# Energy_Shield.net
KiCad netlist of a schematic drawn in EAGLE
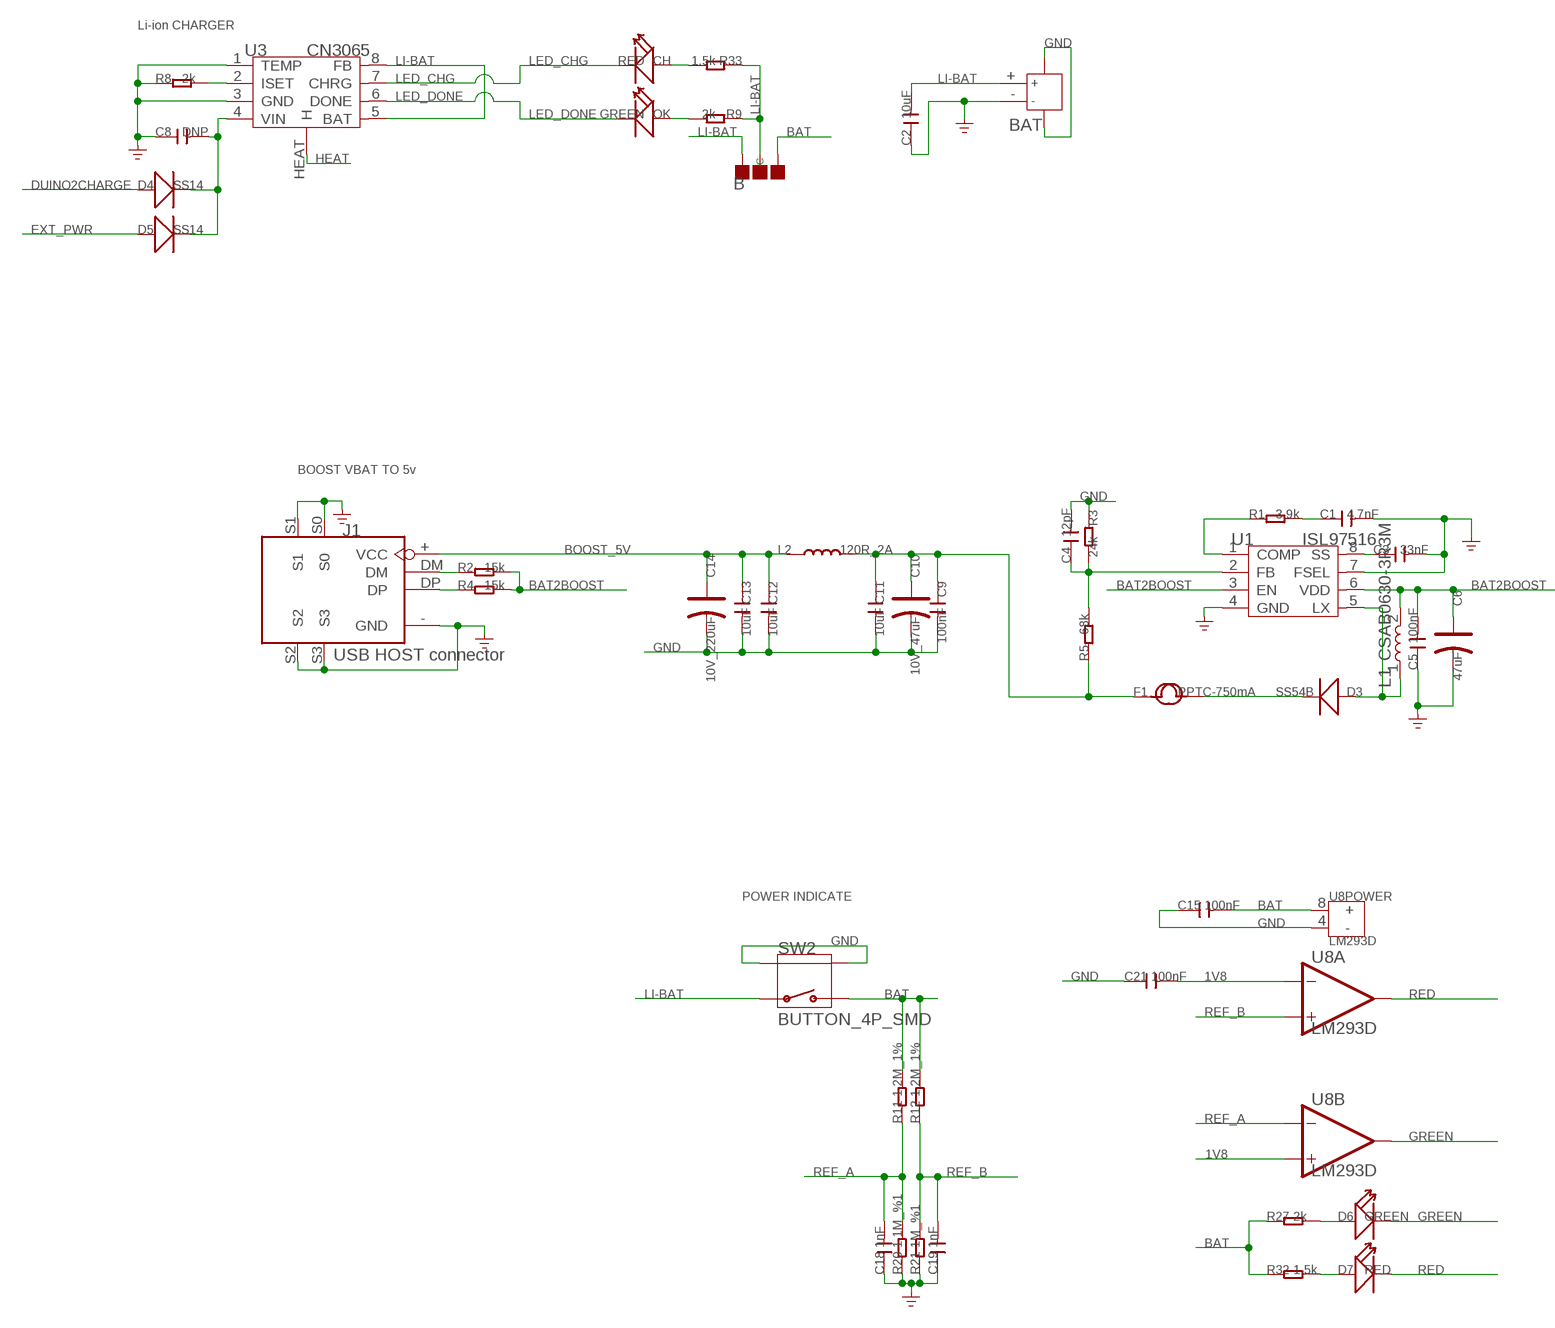
[diagram p0: schematic, sheet 1, part 1 of 2]
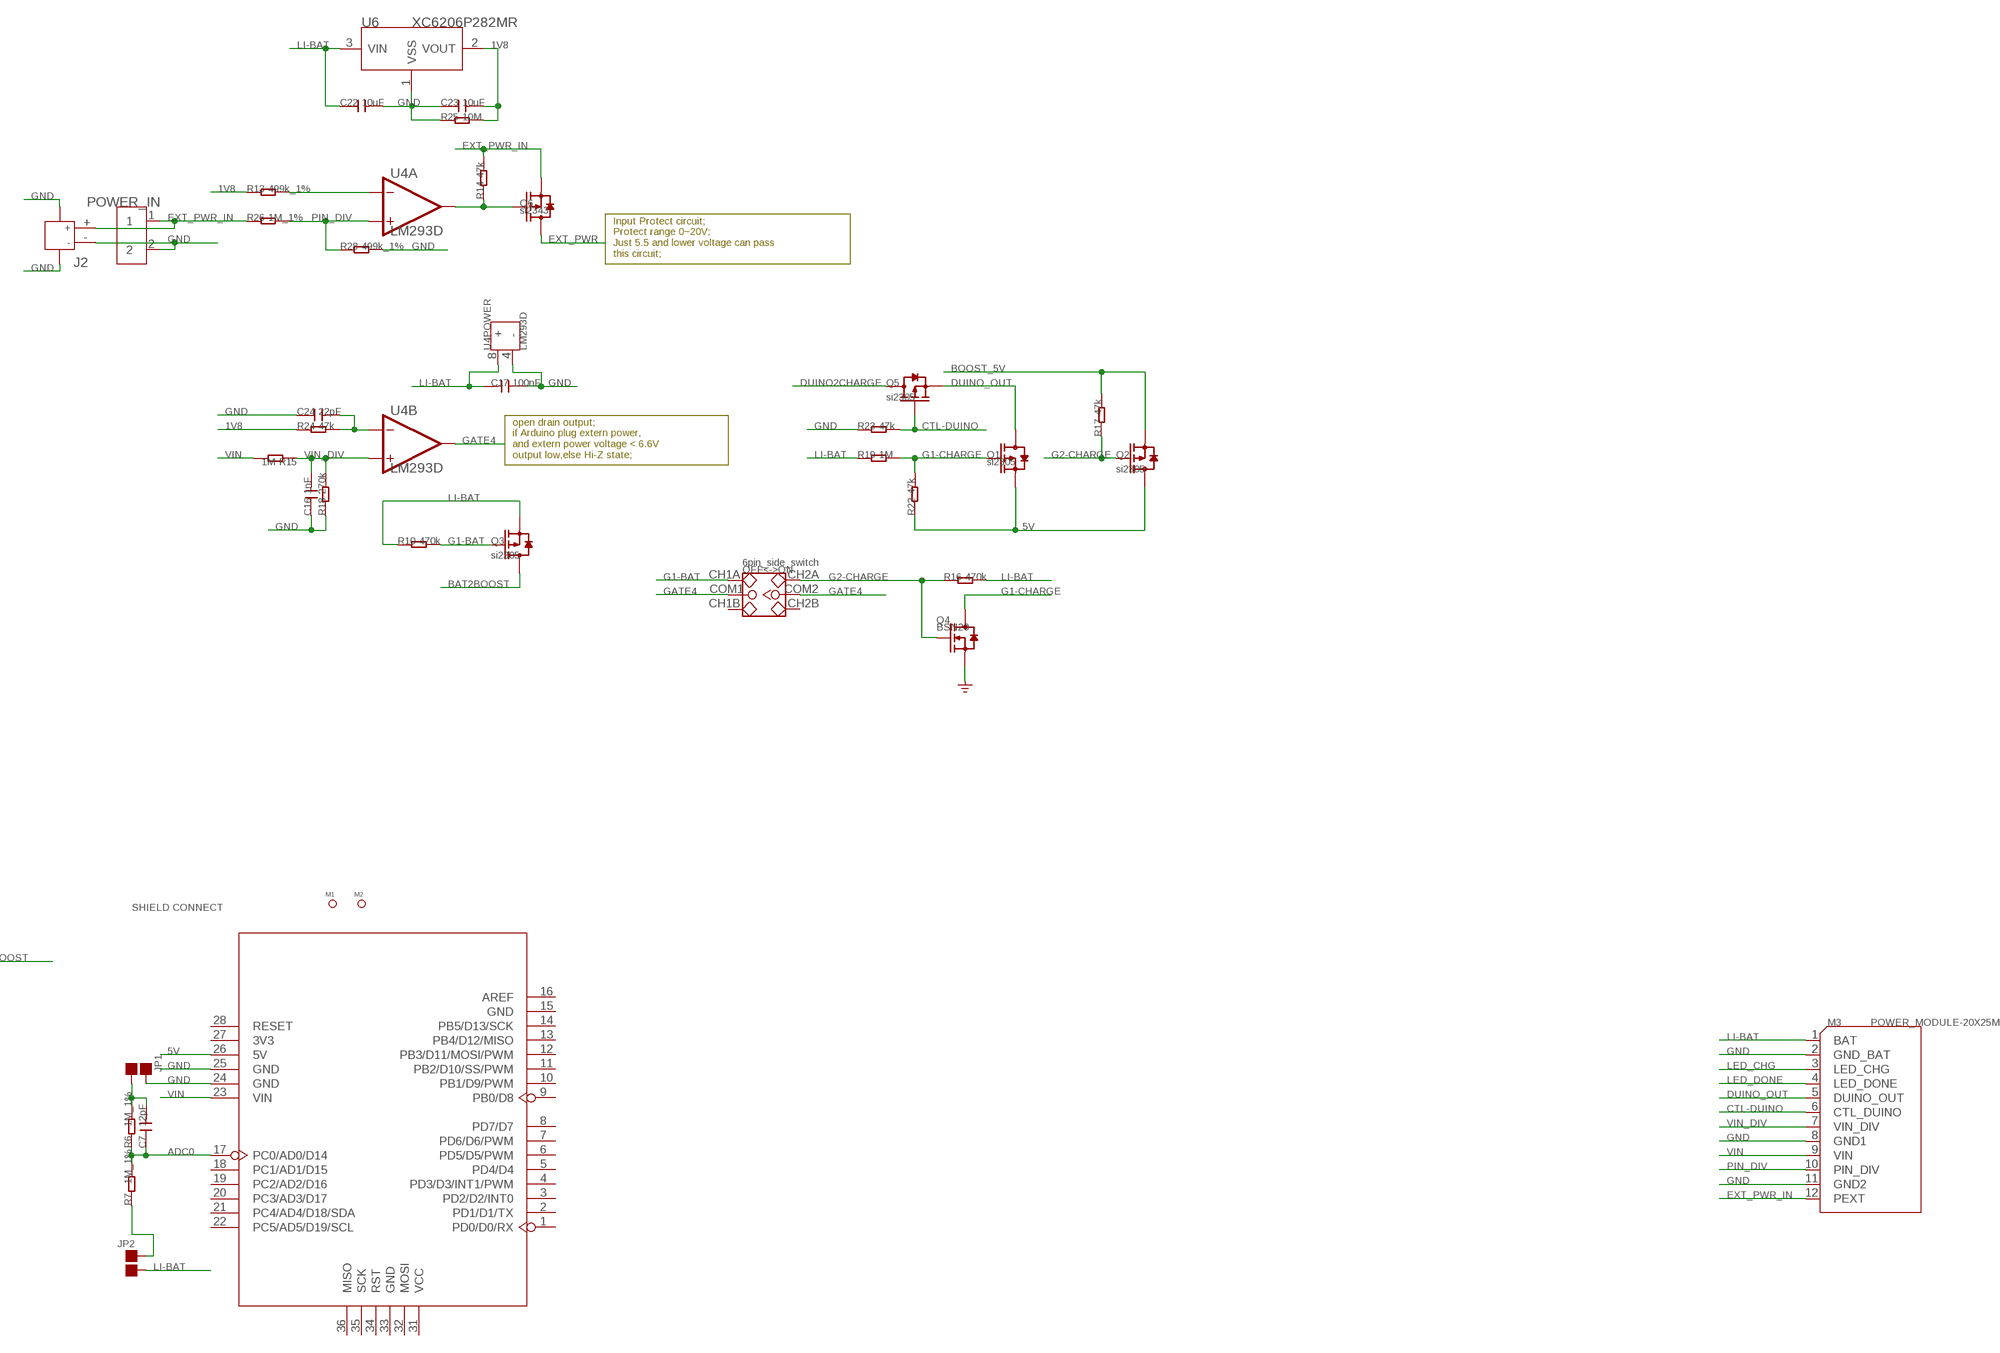
[diagram p1: schematic, sheet 1, part 2 of 2]

(export (version "E")
  (design (tool "Eeschema 10.0.6"))
  (components
    (comp (ref "B")
      (value "PAD-JUMPER-3P-40*40")
      (footprint "eagle-import:3P-SMD-4.1X1.5")
      (fields (field (name "PARTNO") "DNP"))
      (libsource (lib "eagle-import") (part "PAD-JUMPER-3P-4040"))
    )
    (comp (ref "BAT")
      (value "JACK-JST-2P-SMD-PW'2.0'")
      (footprint "eagle-import:JST-SMD-2.0-90D")
      (libsource (lib "eagle-import") (part "JACK-JST-2P-SMD-PW'2.0'"))
    )
    (comp (ref "C1")
      (value "4.7nF")
      (footprint "eagle-import:C0603")
      (libsource (lib "eagle-import") (part "C-0603"))
    )
    (comp (ref "C2")
      (value "10uF")
      (footprint "eagle-import:C0805")
      (libsource (lib "eagle-import") (part "C-0805"))
    )
    (comp (ref "C3")
      (value "33nF")
      (footprint "eagle-import:C0603")
      (libsource (lib "eagle-import") (part "C-0603"))
    )
    (comp (ref "C4")
      (value "12pF")
      (footprint "eagle-import:C0603")
      (libsource (lib "eagle-import") (part "C-0603"))
    )
    (comp (ref "C5")
      (value "100nF")
      (footprint "eagle-import:C0603")
      (libsource (lib "eagle-import") (part "C-0603"))
    )
    (comp (ref "C6")
      (value "47uF")
      (footprint "eagle-import:AVX-B")
      (libsource (lib "eagle-import") (part "CAP-AVX-B"))
    )
    (comp (ref "C7")
      (value "12pF")
      (footprint "eagle-import:C0603")
      (libsource (lib "eagle-import") (part "C-0603"))
    )
    (comp (ref "C8")
      (value "DNP")
      (footprint "eagle-import:C0805")
      (libsource (lib "eagle-import") (part "C-0805"))
    )
    (comp (ref "C9")
      (value "100nF")
      (footprint "eagle-import:C0603")
      (libsource (lib "eagle-import") (part "C-0603"))
    )
    (comp (ref "C10")
      (value "10V_47uF")
      (footprint "eagle-import:AVX-B")
      (libsource (lib "eagle-import") (part "CAP-AVX-B"))
    )
    (comp (ref "C11")
      (value "10uF")
      (footprint "eagle-import:C0805")
      (libsource (lib "eagle-import") (part "C-0805"))
    )
    (comp (ref "C12")
      (value "10uF")
      (footprint "eagle-import:C0805")
      (libsource (lib "eagle-import") (part "C-0805"))
    )
    (comp (ref "C13")
      (value "10uF")
      (footprint "eagle-import:C0805")
      (libsource (lib "eagle-import") (part "C-0805"))
    )
    (comp (ref "C14")
      (value "10V_220uF")
      (footprint "eagle-import:AVX-D")
      (libsource (lib "eagle-import") (part "CAP-AVX-D"))
    )
    (comp (ref "C15")
      (value "100nF")
      (footprint "eagle-import:C0603")
      (libsource (lib "eagle-import") (part "C-0603"))
    )
    (comp (ref "C16")
      (value "1nF")
      (footprint "eagle-import:C0603")
      (libsource (lib "eagle-import") (part "C-0603"))
    )
    (comp (ref "C17")
      (value "100nF")
      (footprint "eagle-import:C0603")
      (libsource (lib "eagle-import") (part "C-0603"))
    )
    (comp (ref "C18")
      (value "1nF")
      (footprint "eagle-import:C0603")
      (libsource (lib "eagle-import") (part "C-0603"))
    )
    (comp (ref "C19")
      (value "1nF")
      (footprint "eagle-import:C0603")
      (libsource (lib "eagle-import") (part "C-0603"))
    )
    (comp (ref "C21")
      (value "100nF")
      (footprint "eagle-import:C0603")
      (libsource (lib "eagle-import") (part "C-0603"))
    )
    (comp (ref "C22")
      (value "10uF")
      (footprint "eagle-import:C0805")
      (libsource (lib "eagle-import") (part "C-0805"))
    )
    (comp (ref "C23")
      (value "10uF")
      (footprint "eagle-import:C0805")
      (libsource (lib "eagle-import") (part "C-0805"))
    )
    (comp (ref "C24")
      (value "22pF")
      (footprint "eagle-import:C0603")
      (libsource (lib "eagle-import") (part "C-0603"))
    )
    (comp (ref "CH")
      (value "RED")
      (footprint "eagle-import:LED-SIDE-VIEW-0603-RIGHT")
      (libsource (lib "eagle-import") (part "LED'RIGHT'"))
    )
    (comp (ref "D3")
      (value "SS54B")
      (footprint "eagle-import:SMB")
      (libsource (lib "eagle-import") (part "D'MBRS240LT3'"))
    )
    (comp (ref "D4")
      (value "SS14")
      (footprint "eagle-import:D2010")
      (libsource (lib "eagle-import") (part "D'SMA'"))
    )
    (comp (ref "D5")
      (value "SS14")
      (footprint "eagle-import:D2010")
      (libsource (lib "eagle-import") (part "D'SMA'"))
    )
    (comp (ref "D6")
      (value "GREEN")
      (footprint "eagle-import:LED-SIDE-VIEW-0603-RIGHT")
      (libsource (lib "eagle-import") (part "LED'RIGHT'"))
    )
    (comp (ref "D7")
      (value "RED")
      (footprint "eagle-import:LED-SIDE-VIEW-0603-RIGHT")
      (libsource (lib "eagle-import") (part "LED'RIGHT'"))
    )
    (comp (ref "F1")
      (value "PPTC-750mA")
      (footprint "eagle-import:F1210")
      (libsource (lib "eagle-import") (part "FUSE'1210'"))
    )
    (comp (ref "J1")
      (value "USB HOST connector")
      (footprint "eagle-import:FEMALE-14.5X13.2")
      (libsource (lib "eagle-import") (part "USB-FEMALE-13.2X14.5"))
    )
    (comp (ref "J2")
      (value "JACK-JST-2P-SMD-PW'2.0'")
      (footprint "eagle-import:JST-SMD-2.0-90D")
      (libsource (lib "eagle-import") (part "JACK-JST-2P-SMD-PW'2.0'"))
    )
    (comp (ref "JP1")
      (value "PAD-JUMPER-2P")
      (footprint "eagle-import:2P-SMD-1.78X1.27")
      (fields (field (name "PARTNO") "DNP") (field (name "PARTNO_1") "DNP"))
      (libsource (lib "eagle-import") (part "PAD-JUMPER-2P"))
    )
    (comp (ref "JP2")
      (value "PAD-JUMPER-2P")
      (footprint "eagle-import:2P-SMD-1.78X1.27")
      (fields (field (name "PARTNO") "DNP"))
      (libsource (lib "eagle-import") (part "PAD-JUMPER-2P"))
    )
    (comp (ref "L1")
      (value "CSAB0630-3R3M")
      (footprint "eagle-import:L0630")
      (libsource (lib "eagle-import") (part "L"))
    )
    (comp (ref "L2")
      (value "120R_2A")
      (footprint "eagle-import:L0805")
      (libsource (lib "eagle-import") (part "L'0805'"))
    )
    (comp (ref "M1")
      (value "PAD-MARK")
      (footprint "eagle-import:ROUND-MARK-1.0")
      (fields (field (name "PARTNO") "DNP"))
      (libsource (lib "eagle-import") (part "PAD-MARK"))
    )
    (comp (ref "M2")
      (value "PAD-MARK")
      (footprint "eagle-import:ROUND-MARK-1.0")
      (fields (field (name "PARTNO") "DNP"))
      (libsource (lib "eagle-import") (part "PAD-MARK"))
    )
    (comp (ref "M3")
      (value "POWER_MODULE-20X25MM")
      (footprint "eagle-import:POWER_MODULE")
      (libsource (lib "eagle-import") (part "POWER_MODULE-20X25MM"))
    )
    (comp (ref "OFF<->ON")
      (value "6pin_side_switch")
      (footprint "eagle-import:6P-2CH-2.5-9.1X3.5X3.2H-90D")
      (libsource (lib "eagle-import") (part "SWITCH-2CH-6P'90D'"))
    )
    (comp (ref "OK")
      (value "GREEN")
      (footprint "eagle-import:LED-SIDE-VIEW-0603-RIGHT")
      (libsource (lib "eagle-import") (part "LED'RIGHT'"))
    )
    (comp (ref "POWER_IN")
      (value "SCREW-TERMINAL-2P'3.5'")
      (footprint "eagle-import:2P-3.5")
      (libsource (lib "eagle-import") (part "SCREW-TERMINAL-2P'3.5'"))
    )
    (comp (ref "Q1")
      (value "si2305")
      (footprint "eagle-import:SOT23")
      (libsource (lib "eagle-import") (part "MOSFET-P'SI2323CDS/SI2305DS{lt}BR{gt}'"))
    )
    (comp (ref "Q2")
      (value "si2305")
      (footprint "eagle-import:SOT23")
      (libsource (lib "eagle-import") (part "MOSFET-P'SI2323CDS/SI2305DS{lt}BR{gt}'"))
    )
    (comp (ref "Q3")
      (value "si2305")
      (footprint "eagle-import:SOT23")
      (libsource (lib "eagle-import") (part "MOSFET-P'SI2323CDS/SI2305DS{lt}BR{gt}'"))
    )
    (comp (ref "Q4")
      (value "BSN20")
      (footprint "eagle-import:SOT23")
      (libsource (lib "eagle-import") (part "MOSFET-N'SOT23'"))
    )
    (comp (ref "Q5")
      (value "si2305")
      (footprint "eagle-import:SOT23")
      (libsource (lib "eagle-import") (part "MOSFET-P'SI2323CDS/SI2305DS{lt}BR{gt}'"))
    )
    (comp (ref "Q6")
      (value "si2343")
      (footprint "eagle-import:SOT23")
      (libsource (lib "eagle-import") (part "MOSFET-P'SI2323CDS/SI2305DS{lt}BR{gt}'"))
    )
    (comp (ref "R1")
      (value "3.9k")
      (footprint "eagle-import:R0603")
      (libsource (lib "eagle-import") (part "R-0603"))
    )
    (comp (ref "R2")
      (value "15k")
      (footprint "eagle-import:R0603")
      (libsource (lib "eagle-import") (part "R-0603"))
    )
    (comp (ref "R3")
      (value "24k")
      (footprint "eagle-import:R0603")
      (libsource (lib "eagle-import") (part "R-0603"))
    )
    (comp (ref "R4")
      (value "15k")
      (footprint "eagle-import:R0603")
      (libsource (lib "eagle-import") (part "R-0603"))
    )
    (comp (ref "R5")
      (value "68k")
      (footprint "eagle-import:R0603")
      (libsource (lib "eagle-import") (part "R-0603"))
    )
    (comp (ref "R6")
      (value "1M_1%")
      (footprint "eagle-import:R0603")
      (libsource (lib "eagle-import") (part "R-0603"))
    )
    (comp (ref "R7")
      (value "1M_1%")
      (footprint "eagle-import:R0603")
      (libsource (lib "eagle-import") (part "R-0603"))
    )
    (comp (ref "R8")
      (value "2k")
      (footprint "eagle-import:R0603")
      (libsource (lib "eagle-import") (part "R-0603"))
    )
    (comp (ref "R9")
      (value "2k")
      (footprint "eagle-import:R0603")
      (libsource (lib "eagle-import") (part "R-0603"))
    )
    (comp (ref "R10")
      (value "470k")
      (footprint "eagle-import:R0603")
      (libsource (lib "eagle-import") (part "R-0603"))
    )
    (comp (ref "R11")
      (value "1.2M_1%")
      (footprint "eagle-import:R0603")
      (libsource (lib "eagle-import") (part "R-0603"))
    )
    (comp (ref "R12")
      (value "1.2M_1%")
      (footprint "eagle-import:R0603")
      (libsource (lib "eagle-import") (part "R-0603"))
    )
    (comp (ref "R13")
      (value "499k_1%")
      (footprint "eagle-import:R0603")
      (libsource (lib "eagle-import") (part "R-0603"))
    )
    (comp (ref "R14")
      (value "47k")
      (footprint "eagle-import:R0603")
      (libsource (lib "eagle-import") (part "R-0603"))
    )
    (comp (ref "R15")
      (value "1M")
      (footprint "eagle-import:R0603")
      (libsource (lib "eagle-import") (part "R-0603"))
    )
    (comp (ref "R16")
      (value "470k")
      (footprint "eagle-import:R0603")
      (libsource (lib "eagle-import") (part "R-0603"))
    )
    (comp (ref "R17")
      (value "47k")
      (footprint "eagle-import:R0603")
      (libsource (lib "eagle-import") (part "R-0603"))
    )
    (comp (ref "R18")
      (value "270k")
      (footprint "eagle-import:R0603")
      (libsource (lib "eagle-import") (part "R-0603"))
    )
    (comp (ref "R19")
      (value "1M")
      (footprint "eagle-import:R0603")
      (libsource (lib "eagle-import") (part "R-0603"))
    )
    (comp (ref "R20")
      (value "1.1M_%1")
      (footprint "eagle-import:R0603")
      (libsource (lib "eagle-import") (part "R-0603"))
    )
    (comp (ref "R21")
      (value "1M_%1")
      (footprint "eagle-import:R0603")
      (libsource (lib "eagle-import") (part "R-0603"))
    )
    (comp (ref "R22")
      (value "47k")
      (footprint "eagle-import:R0603")
      (libsource (lib "eagle-import") (part "R-0603"))
    )
    (comp (ref "R23")
      (value "47k")
      (footprint "eagle-import:R0603")
      (libsource (lib "eagle-import") (part "R-0603"))
    )
    (comp (ref "R24")
      (value "47k")
      (footprint "eagle-import:R0603")
      (libsource (lib "eagle-import") (part "R-0603"))
    )
    (comp (ref "R25")
      (value "10M")
      (footprint "eagle-import:R0603")
      (libsource (lib "eagle-import") (part "R-0603"))
    )
    (comp (ref "R26")
      (value "1M_1%")
      (footprint "eagle-import:R0603")
      (libsource (lib "eagle-import") (part "R-0603"))
    )
    (comp (ref "R27")
      (value "2k")
      (footprint "eagle-import:R0603")
      (libsource (lib "eagle-import") (part "R-0603"))
    )
    (comp (ref "R28")
      (value "499k_1%")
      (footprint "eagle-import:R0603")
      (libsource (lib "eagle-import") (part "R-0603"))
    )
    (comp (ref "R32")
      (value "1.5k")
      (footprint "eagle-import:R0603")
      (libsource (lib "eagle-import") (part "R-0603"))
    )
    (comp (ref "R33")
      (value "1.5k")
      (footprint "eagle-import:R0603")
      (libsource (lib "eagle-import") (part "R-0603"))
    )
    (comp (ref "SW2")
      (value "BUTTON_4P_SMD")
      (footprint "eagle-import:4P-SMD-7X3.5X3.5")
      (libsource (lib "eagle-import") (part "BUTTON_4P_SMD"))
    )
    (comp (ref "U1")
      (value "ISL97516")
      (footprint "eagle-import:MSOP8")
      (libsource (lib "eagle-import") (part "ISL97516-MSOP8"))
    )
    (comp (ref "U2")
      (value "ARDUINO'W/O-SILK'")
      (footprint "eagle-import:ARDUINO-W_O-SILK")
      (libsource (lib "eagle-import") (part "ARDUINO'W/O-SILK'"))
    )
    (comp (ref "U3")
      (value "CN3065")
      (footprint "eagle-import:DFN8")
      (libsource (lib "eagle-import") (part "CN3065-DFN8"))
    )
    (comp (ref "U4")
      (value "LM293D")
      (footprint "eagle-import:SOIC8-6.0")
      (libsource (lib "eagle-import") (part "LMX93D"))
    )
    (comp (ref "U6")
      (value "XC6206P282MR")
      (footprint "eagle-import:SOT23")
      (libsource (lib "eagle-import") (part "XC6206MR"))
    )
    (comp (ref "U8")
      (value "LM293D")
      (footprint "eagle-import:SOIC8-6.0")
      (libsource (lib "eagle-import") (part "LMX93D"))
    )
  )
  (nets
    (net (code "1") (name "/1V8") (class "Default")
      (node (ref "C21") (pin "2") (pinfunction "2_2") (pintype "passive"))
      (node (ref "C23") (pin "2") (pinfunction "2_2") (pintype "passive"))
      (node (ref "R13") (pin "1") (pinfunction "1_1") (pintype "passive"))
      (node (ref "R24") (pin "1") (pinfunction "1_1") (pintype "passive"))
      (node (ref "R25") (pin "2") (pinfunction "2_2") (pintype "passive"))
      (node (ref "U6") (pin "2") (pinfunction "VOUT_2") (pintype "output"))
      (node (ref "U8") (pin "2") (pinfunction "IN-_2") (pintype "input"))
      (node (ref "U8") (pin "5") (pinfunction "IN+_5") (pintype "input"))
    )
    (net (code "2") (name "/5V") (class "Default")
      (node (ref "Q1") (pin "2") (pinfunction "S_2") (pintype "passive"))
      (node (ref "Q2") (pin "3") (pinfunction "D_3") (pintype "passive"))
      (node (ref "R22") (pin "1") (pinfunction "1_1") (pintype "passive"))
      (node (ref "U2") (pin "26") (pinfunction "5V_26") (pintype "bidirectional"))
    )
    (net (code "3") (name "/ADC0") (class "Default")
      (node (ref "C7") (pin "1") (pinfunction "1_1") (pintype "passive"))
      (node (ref "R6") (pin "1") (pinfunction "1_1") (pintype "passive"))
      (node (ref "R7") (pin "2") (pinfunction "2_2") (pintype "passive"))
      (node (ref "U2") (pin "17") (pinfunction "PC0/AD0/D14_17") (pintype "bidirectional"))
    )
    (net (code "4") (name "/BAT") (class "Default")
      (node (ref "B") (pin "00") (pinfunction "L_00") (pintype "bidirectional"))
      (node (ref "C15") (pin "2") (pinfunction "2_2") (pintype "passive"))
      (node (ref "R11") (pin "2") (pinfunction "2_2") (pintype "passive"))
      (node (ref "R12") (pin "2") (pinfunction "2_2") (pintype "passive"))
      (node (ref "R27") (pin "1") (pinfunction "1_1") (pintype "passive"))
      (node (ref "R32") (pin "1") (pinfunction "1_1") (pintype "passive"))
      (node (ref "SW2") (pin "2") (pinfunction "2_2") (pintype "bidirectional"))
      (node (ref "U8") (pin "8") (pinfunction "+_8") (pintype "bidirectional"))
    )
    (net (code "5") (name "/BAT2BOOST") (class "Default")
      (node (ref "C5") (pin "2") (pinfunction "2_2") (pintype "passive"))
      (node (ref "C6") (pin "+") (pinfunction "+_+") (pintype "passive"))
      (node (ref "L1") (pin "2") (pinfunction "P$2_2") (pintype "bidirectional"))
      (node (ref "Q3") (pin "3") (pinfunction "D_3") (pintype "passive"))
      (node (ref "R2") (pin "2") (pinfunction "2_2") (pintype "passive"))
      (node (ref "R4") (pin "2") (pinfunction "2_2") (pintype "passive"))
      (node (ref "U1") (pin "3") (pinfunction "EN_3") (pintype "input"))
      (node (ref "U1") (pin "6") (pinfunction "VDD_6") (pintype "power_in"))
    )
    (net (code "6") (name "/BOOST_5V") (class "Default")
      (node (ref "C12") (pin "1") (pinfunction "1_1") (pintype "passive"))
      (node (ref "C13") (pin "1") (pinfunction "1_1") (pintype "passive"))
      (node (ref "C14") (pin "+") (pinfunction "+_+") (pintype "passive"))
      (node (ref "J1") (pin "+") (pinfunction "VCC_+") (pintype "bidirectional"))
      (node (ref "L2") (pin "1") (pinfunction "1_1") (pintype "passive"))
      (node (ref "Q2") (pin "2") (pinfunction "S_2") (pintype "passive"))
      (node (ref "R17") (pin "2") (pinfunction "2_2") (pintype "passive"))
    )
    (net (code "7") (name "/CTL-DUINO") (class "Default")
      (node (ref "M3") (pin "6") (pinfunction "CTL_DUINO_6") (pintype "bidirectional"))
      (node (ref "Q5") (pin "1") (pinfunction "G_1") (pintype "passive"))
      (node (ref "R23") (pin "2") (pinfunction "2_2") (pintype "passive"))
    )
    (net (code "8") (name "/DUINO2CHARGE") (class "Default")
      (node (ref "D4") (pin "+") (pinfunction "+_+") (pintype "passive"))
      (node (ref "Q5") (pin "3") (pinfunction "D_3") (pintype "passive"))
    )
    (net (code "9") (name "/DUINO_OUT") (class "Default")
      (node (ref "M3") (pin "5") (pinfunction "DUINO_OUT_5") (pintype "bidirectional"))
      (node (ref "Q1") (pin "3") (pinfunction "D_3") (pintype "passive"))
      (node (ref "Q5") (pin "2") (pinfunction "S_2") (pintype "passive"))
    )
    (net (code "10") (name "/EXT_PWR") (class "Default")
      (node (ref "D5") (pin "+") (pinfunction "+_+") (pintype "passive"))
      (node (ref "Q6") (pin "3") (pinfunction "D_3") (pintype "passive"))
    )
    (net (code "11") (name "/EXT_PWR_IN") (class "Default")
      (node (ref "J2") (pin "+") (pinfunction "1_+") (pintype "bidirectional"))
      (node (ref "M3") (pin "12") (pinfunction "PEXT_12") (pintype "bidirectional"))
      (node (ref "POWER_IN") (pin "1") (pinfunction "1_1") (pintype "bidirectional"))
      (node (ref "Q6") (pin "2") (pinfunction "S_2") (pintype "passive"))
      (node (ref "R14") (pin "2") (pinfunction "2_2") (pintype "passive"))
      (node (ref "R26") (pin "1") (pinfunction "1_1") (pintype "passive"))
    )
    (net (code "12") (name "/G1-BAT") (class "Default")
      (node (ref "OFF<->ON") (pin "CH1A") (pinfunction "CH1A_CH1A") (pintype "bidirectional"))
      (node (ref "Q3") (pin "1") (pinfunction "G_1") (pintype "passive"))
      (node (ref "R10") (pin "2") (pinfunction "2_2") (pintype "passive"))
    )
    (net (code "13") (name "/G1-CHARGE") (class "Default")
      (node (ref "Q1") (pin "1") (pinfunction "G_1") (pintype "passive"))
      (node (ref "Q4") (pin "3") (pinfunction "D_3") (pintype "passive"))
      (node (ref "R19") (pin "2") (pinfunction "2_2") (pintype "passive"))
      (node (ref "R22") (pin "2") (pinfunction "2_2") (pintype "passive"))
    )
    (net (code "14") (name "/G2-CHARGE") (class "Default")
      (node (ref "OFF<->ON") (pin "CH2A") (pinfunction "CH2A_CH2A") (pintype "bidirectional"))
      (node (ref "Q2") (pin "1") (pinfunction "G_1") (pintype "passive"))
      (node (ref "Q4") (pin "1") (pinfunction "G_1") (pintype "passive"))
      (node (ref "R16") (pin "1") (pinfunction "1_1") (pintype "passive"))
      (node (ref "R17") (pin "1") (pinfunction "1_1") (pintype "passive"))
    )
    (net (code "15") (name "/GATE4") (class "Default")
      (node (ref "OFF<->ON") (pin "COM1") (pinfunction "COM1_COM1") (pintype "bidirectional"))
      (node (ref "OFF<->ON") (pin "COM2") (pinfunction "COM2_COM2") (pintype "bidirectional"))
      (node (ref "U4") (pin "7") (pinfunction "OUT_7") (pintype "output"))
    )
    (net (code "16") (name "/GREEN") (class "Default")
      (node (ref "D6") (pin "2") (pinfunction "-_2") (pintype "passive"))
      (node (ref "U8") (pin "7") (pinfunction "OUT_7") (pintype "output"))
    )
    (net (code "17") (name "/HEAT") (class "Default")
      (node (ref "U3") (pin "HEAT") (pinfunction "H_HEAT") (pintype "bidirectional"))
    )
    (net (code "18") (name "/LED_CHG") (class "Default")
      (node (ref "CH") (pin "2") (pinfunction "-_2") (pintype "passive"))
      (node (ref "M3") (pin "3") (pinfunction "LED_CHG_3") (pintype "bidirectional"))
      (node (ref "U3") (pin "7") (pinfunction "CHRG_7") (pintype "bidirectional"))
    )
    (net (code "19") (name "/LED_DONE") (class "Default")
      (node (ref "M3") (pin "4") (pinfunction "LED_DONE_4") (pintype "bidirectional"))
      (node (ref "OK") (pin "2") (pinfunction "-_2") (pintype "passive"))
      (node (ref "U3") (pin "6") (pinfunction "DONE_6") (pintype "bidirectional"))
    )
    (net (code "20") (name "/LI-BAT") (class "Default")
      (node (ref "B") (pin "11") (pinfunction "R_11") (pintype "bidirectional"))
      (node (ref "B") (pin "MM") (pinfunction "C_MM") (pintype "bidirectional"))
      (node (ref "BAT") (pin "+") (pinfunction "1_+") (pintype "bidirectional"))
      (node (ref "C17") (pin "2") (pinfunction "2_2") (pintype "passive"))
      (node (ref "C2") (pin "2") (pinfunction "2_2") (pintype "passive"))
      (node (ref "C22") (pin "1") (pinfunction "1_1") (pintype "passive"))
      (node (ref "JP2") (pin "1") (pinfunction "1_1") (pintype "bidirectional"))
      (node (ref "M3") (pin "1") (pinfunction "BAT_1") (pintype "bidirectional"))
      (node (ref "Q3") (pin "2") (pinfunction "S_2") (pintype "passive"))
      (node (ref "R10") (pin "1") (pinfunction "1_1") (pintype "passive"))
      (node (ref "R16") (pin "2") (pinfunction "2_2") (pintype "passive"))
      (node (ref "R19") (pin "1") (pinfunction "1_1") (pintype "passive"))
      (node (ref "R33") (pin "1") (pinfunction "1_1") (pintype "passive"))
      (node (ref "R9") (pin "1") (pinfunction "1_1") (pintype "passive"))
      (node (ref "SW2") (pin "1") (pinfunction "1_1") (pintype "bidirectional"))
      (node (ref "U3") (pin "5") (pinfunction "BAT_5") (pintype "bidirectional"))
      (node (ref "U3") (pin "8") (pinfunction "FB_8") (pintype "input"))
      (node (ref "U4") (pin "8") (pinfunction "+_8") (pintype "bidirectional"))
      (node (ref "U6") (pin "3") (pinfunction "VIN_3") (pintype "input"))
    )
    (net (code "21") (name "/PIN_DIV") (class "Default")
      (node (ref "M3") (pin "10") (pinfunction "PIN_DIV_10") (pintype "bidirectional"))
      (node (ref "R26") (pin "2") (pinfunction "2_2") (pintype "passive"))
      (node (ref "R28") (pin "1") (pinfunction "1_1") (pintype "passive"))
      (node (ref "U4") (pin "3") (pinfunction "IN+_3") (pintype "input"))
    )
    (net (code "22") (name "/RED") (class "Default")
      (node (ref "D7") (pin "2") (pinfunction "-_2") (pintype "passive"))
      (node (ref "U8") (pin "1") (pinfunction "OUT_1") (pintype "output"))
    )
    (net (code "23") (name "/REF_A") (class "Default")
      (node (ref "C18") (pin "2") (pinfunction "2_2") (pintype "passive"))
      (node (ref "R11") (pin "1") (pinfunction "1_1") (pintype "passive"))
      (node (ref "R20") (pin "2") (pinfunction "2_2") (pintype "passive"))
      (node (ref "U8") (pin "6") (pinfunction "IN-_6") (pintype "input"))
    )
    (net (code "24") (name "/REF_B") (class "Default")
      (node (ref "C19") (pin "2") (pinfunction "2_2") (pintype "passive"))
      (node (ref "R12") (pin "1") (pinfunction "1_1") (pintype "passive"))
      (node (ref "R21") (pin "2") (pinfunction "2_2") (pintype "passive"))
      (node (ref "U8") (pin "3") (pinfunction "IN+_3") (pintype "input"))
    )
    (net (code "25") (name "/VIN") (class "Default")
      (node (ref "M3") (pin "9") (pinfunction "VIN_9") (pintype "bidirectional"))
      (node (ref "R15") (pin "2") (pinfunction "2_2") (pintype "passive"))
      (node (ref "U2") (pin "23") (pinfunction "VIN_23") (pintype "bidirectional"))
    )
    (net (code "26") (name "/VIN_DIV") (class "Default")
      (node (ref "C16") (pin "2") (pinfunction "2_2") (pintype "passive"))
      (node (ref "M3") (pin "7") (pinfunction "VIN_DIV_7") (pintype "bidirectional"))
      (node (ref "R15") (pin "1") (pinfunction "1_1") (pintype "passive"))
      (node (ref "R18") (pin "2") (pinfunction "2_2") (pintype "passive"))
      (node (ref "U4") (pin "5") (pinfunction "IN+_5") (pintype "input"))
    )
    (net (code "27") (name "GND_POWER") (class "Default")
      (node (ref "BAT") (pin "-") (pinfunction "2_-") (pintype "bidirectional"))
      (node (ref "BAT") (pin "3") (pinfunction "3_3") (pintype "bidirectional"))
      (node (ref "BAT") (pin "4") (pinfunction "4_4") (pintype "bidirectional"))
      (node (ref "C1") (pin "2") (pinfunction "2_2") (pintype "passive"))
      (node (ref "C10") (pin "-") (pinfunction "-_-") (pintype "passive"))
      (node (ref "C11") (pin "2") (pinfunction "2_2") (pintype "passive"))
      (node (ref "C12") (pin "2") (pinfunction "2_2") (pintype "passive"))
      (node (ref "C13") (pin "2") (pinfunction "2_2") (pintype "passive"))
      (node (ref "C14") (pin "-") (pinfunction "-_-") (pintype "passive"))
      (node (ref "C15") (pin "1") (pinfunction "1_1") (pintype "passive"))
      (node (ref "C16") (pin "1") (pinfunction "1_1") (pintype "passive"))
      (node (ref "C17") (pin "1") (pinfunction "1_1") (pintype "passive"))
      (node (ref "C18") (pin "1") (pinfunction "1_1") (pintype "passive"))
      (node (ref "C19") (pin "1") (pinfunction "1_1") (pintype "passive"))
      (node (ref "C2") (pin "1") (pinfunction "1_1") (pintype "passive"))
      (node (ref "C21") (pin "1") (pinfunction "1_1") (pintype "passive"))
      (node (ref "C22") (pin "2") (pinfunction "2_2") (pintype "passive"))
      (node (ref "C23") (pin "1") (pinfunction "1_1") (pintype "passive"))
      (node (ref "C24") (pin "1") (pinfunction "1_1") (pintype "passive"))
      (node (ref "C3") (pin "2") (pinfunction "2_2") (pintype "passive"))
      (node (ref "C4") (pin "2") (pinfunction "2_2") (pintype "passive"))
      (node (ref "C5") (pin "1") (pinfunction "1_1") (pintype "passive"))
      (node (ref "C6") (pin "-") (pinfunction "-_-") (pintype "passive"))
      (node (ref "C8") (pin "1") (pinfunction "1_1") (pintype "passive"))
      (node (ref "C9") (pin "2") (pinfunction "2_2") (pintype "passive"))
      (node (ref "J1") (pin "-") (pinfunction "GND_-") (pintype "bidirectional"))
      (node (ref "J1") (pin "S0") (pinfunction "S0_S0") (pintype "bidirectional"))
      (node (ref "J1") (pin "S1") (pinfunction "S1_S1") (pintype "bidirectional"))
      (node (ref "J1") (pin "S2") (pinfunction "S2_S2") (pintype "bidirectional"))
      (node (ref "J1") (pin "S3") (pinfunction "S3_S3") (pintype "bidirectional"))
      (node (ref "J2") (pin "-") (pinfunction "2_-") (pintype "bidirectional"))
      (node (ref "J2") (pin "3") (pinfunction "3_3") (pintype "bidirectional"))
      (node (ref "J2") (pin "4") (pinfunction "4_4") (pintype "bidirectional"))
      (node (ref "JP1") (pin "2") (pinfunction "2_2") (pintype "bidirectional"))
      (node (ref "M3") (pin "11") (pinfunction "GND2_11") (pintype "bidirectional"))
      (node (ref "M3") (pin "2") (pinfunction "GND_BAT_2") (pintype "bidirectional"))
      (node (ref "M3") (pin "8") (pinfunction "GND1_8") (pintype "bidirectional"))
      (node (ref "POWER_IN") (pin "2") (pinfunction "2_2") (pintype "bidirectional"))
      (node (ref "Q4") (pin "2") (pinfunction "S_2") (pintype "passive"))
      (node (ref "R18") (pin "1") (pinfunction "1_1") (pintype "passive"))
      (node (ref "R20") (pin "1") (pinfunction "1_1") (pintype "passive"))
      (node (ref "R21") (pin "1") (pinfunction "1_1") (pintype "passive"))
      (node (ref "R23") (pin "1") (pinfunction "1_1") (pintype "passive"))
      (node (ref "R25") (pin "1") (pinfunction "1_1") (pintype "passive"))
      (node (ref "R28") (pin "2") (pinfunction "2_2") (pintype "passive"))
      (node (ref "R3") (pin "1") (pinfunction "1_1") (pintype "passive"))
      (node (ref "R8") (pin "1") (pinfunction "1_1") (pintype "passive"))
      (node (ref "SW2") (pin "S1") (pinfunction "S1_S1") (pintype "bidirectional"))
      (node (ref "SW2") (pin "S2") (pinfunction "S2_S2") (pintype "bidirectional"))
      (node (ref "U1") (pin "4") (pinfunction "GND_4") (pintype "power_in"))
      (node (ref "U1") (pin "7") (pinfunction "FSEL_7") (pintype "bidirectional"))
      (node (ref "U2") (pin "24") (pinfunction "GND_24") (pintype "bidirectional"))
      (node (ref "U2") (pin "25") (pinfunction "GND_25") (pintype "bidirectional"))
      (node (ref "U3") (pin "1") (pinfunction "TEMP_1") (pintype "input"))
      (node (ref "U3") (pin "3") (pinfunction "GND_3") (pintype "power_in"))
      (node (ref "U4") (pin "4") (pinfunction "-_4") (pintype "bidirectional"))
      (node (ref "U6") (pin "1") (pinfunction "VSS_1") (pintype "power_in"))
      (node (ref "U8") (pin "4") (pinfunction "-_4") (pintype "bidirectional"))
    )
    (net (code "28") (name "Net-(C1-Pad1)") (class "Default")
      (node (ref "C1") (pin "1") (pinfunction "1_1") (pintype "passive"))
      (node (ref "R1") (pin "2") (pinfunction "2_2") (pintype "passive"))
    )
    (net (code "29") (name "Net-(C7-Pad2)") (class "Default")
      (node (ref "C7") (pin "2") (pinfunction "2_2") (pintype "passive"))
      (node (ref "JP1") (pin "1") (pinfunction "1_1") (pintype "bidirectional"))
      (node (ref "R6") (pin "2") (pinfunction "2_2") (pintype "passive"))
    )
    (net (code "30") (name "Net-(C10-Pad+)") (class "Default")
      (node (ref "C10") (pin "+") (pinfunction "+_+") (pintype "passive"))
      (node (ref "C11") (pin "1") (pinfunction "1_1") (pintype "passive"))
      (node (ref "C9") (pin "1") (pinfunction "1_1") (pintype "passive"))
      (node (ref "F1") (pin "1") (pinfunction "1_1") (pintype "bidirectional"))
      (node (ref "L2") (pin "2") (pinfunction "2_2") (pintype "passive"))
      (node (ref "R5") (pin "1") (pinfunction "1_1") (pintype "passive"))
    )
    (net (code "31") (name "Net-(CH-+)") (class "Default")
      (node (ref "CH") (pin "1") (pinfunction "+_1") (pintype "passive"))
      (node (ref "R33") (pin "2") (pinfunction "2_2") (pintype "passive"))
    )
    (net (code "32") (name "Net-(D3-Pad-)") (class "Default")
      (node (ref "D3") (pin "-") (pinfunction "-_-") (pintype "passive"))
      (node (ref "F1") (pin "2") (pinfunction "2_2") (pintype "bidirectional"))
    )
    (net (code "33") (name "Net-(D6-+)") (class "Default")
      (node (ref "D6") (pin "1") (pinfunction "+_1") (pintype "passive"))
      (node (ref "R27") (pin "2") (pinfunction "2_2") (pintype "passive"))
    )
    (net (code "34") (name "Net-(D7-+)") (class "Default")
      (node (ref "D7") (pin "1") (pinfunction "+_1") (pintype "passive"))
      (node (ref "R32") (pin "2") (pinfunction "2_2") (pintype "passive"))
    )
    (net (code "35") (name "Net-(J1-PadDM)") (class "Default")
      (node (ref "J1") (pin "DM") (pinfunction "DM_DM") (pintype "bidirectional"))
      (node (ref "R2") (pin "1") (pinfunction "1_1") (pintype "passive"))
    )
    (net (code "36") (name "Net-(J1-PadDP)") (class "Default")
      (node (ref "J1") (pin "DP") (pinfunction "DP_DP") (pintype "bidirectional"))
      (node (ref "R4") (pin "1") (pinfunction "1_1") (pintype "passive"))
    )
    (net (code "37") (name "Net-(JP2-Pad2)") (class "Default")
      (node (ref "JP2") (pin "2") (pinfunction "2_2") (pintype "bidirectional"))
      (node (ref "R7") (pin "1") (pinfunction "1_1") (pintype "passive"))
    )
    (net (code "38") (name "Net-(L1-P$1)") (class "Default")
      (node (ref "D3") (pin "+") (pinfunction "+_+") (pintype "passive"))
      (node (ref "L1") (pin "1") (pinfunction "P$1_1") (pintype "bidirectional"))
      (node (ref "U1") (pin "5") (pinfunction "LX_5") (pintype "output"))
    )
    (net (code "39") (name "Net-(OK-+)") (class "Default")
      (node (ref "OK") (pin "1") (pinfunction "+_1") (pintype "passive"))
      (node (ref "R9") (pin "2") (pinfunction "2_2") (pintype "passive"))
    )
    (net (code "40") (name "Net-(Q6-G)") (class "Default")
      (node (ref "Q6") (pin "1") (pinfunction "G_1") (pintype "passive"))
      (node (ref "R14") (pin "1") (pinfunction "1_1") (pintype "passive"))
      (node (ref "U4") (pin "1") (pinfunction "OUT_1") (pintype "output"))
    )
    (net (code "41") (name "Net-(U1-COMP)") (class "Default")
      (node (ref "R1") (pin "1") (pinfunction "1_1") (pintype "passive"))
      (node (ref "U1") (pin "1") (pinfunction "COMP_1") (pintype "bidirectional"))
    )
    (net (code "42") (name "Net-(U1-FB)") (class "Default")
      (node (ref "C4") (pin "1") (pinfunction "1_1") (pintype "passive"))
      (node (ref "R3") (pin "2") (pinfunction "2_2") (pintype "passive"))
      (node (ref "R5") (pin "2") (pinfunction "2_2") (pintype "passive"))
      (node (ref "U1") (pin "2") (pinfunction "FB_2") (pintype "input"))
    )
    (net (code "43") (name "Net-(U1-SS)") (class "Default")
      (node (ref "C3") (pin "1") (pinfunction "1_1") (pintype "passive"))
      (node (ref "U1") (pin "8") (pinfunction "SS_8") (pintype "bidirectional"))
    )
    (net (code "44") (name "Net-(U3-ISET)") (class "Default")
      (node (ref "R8") (pin "2") (pinfunction "2_2") (pintype "passive"))
      (node (ref "U3") (pin "2") (pinfunction "ISET_2") (pintype "bidirectional"))
    )
    (net (code "45") (name "Net-(U3-VIN)") (class "Default")
      (node (ref "C8") (pin "2") (pinfunction "2_2") (pintype "passive"))
      (node (ref "D4") (pin "-") (pinfunction "-_-") (pintype "passive"))
      (node (ref "D5") (pin "-") (pinfunction "-_-") (pintype "passive"))
      (node (ref "U3") (pin "4") (pinfunction "VIN_4") (pintype "input"))
    )
    (net (code "46") (name "Net-(U4A-IN-)") (class "Default")
      (node (ref "R13") (pin "2") (pinfunction "2_2") (pintype "passive"))
      (node (ref "U4") (pin "2") (pinfunction "IN-_2") (pintype "input"))
    )
    (net (code "47") (name "Net-(U4B-IN-)") (class "Default")
      (node (ref "C24") (pin "2") (pinfunction "2_2") (pintype "passive"))
      (node (ref "R24") (pin "2") (pinfunction "2_2") (pintype "passive"))
      (node (ref "U4") (pin "6") (pinfunction "IN-_6") (pintype "input"))
    )
    (net (code "48") (name "unconnected-(OFF<->ON-PadCH1B)") (class "Default")
      (node (ref "OFF<->ON") (pin "CH1B") (pinfunction "CH1B_CH1B") (pintype "bidirectional"))
    )
    (net (code "49") (name "unconnected-(OFF<->ON-PadCH2B)") (class "Default")
      (node (ref "OFF<->ON") (pin "CH2B") (pinfunction "CH2B_CH2B") (pintype "bidirectional"))
    )
    (net (code "50") (name "unconnected-(U2-3V3-Pad27)") (class "Default")
      (node (ref "U2") (pin "27") (pinfunction "3V3_27") (pintype "bidirectional"))
    )
    (net (code "51") (name "unconnected-(U2-AREF-Pad16)") (class "Default")
      (node (ref "U2") (pin "16") (pinfunction "AREF_16") (pintype "bidirectional"))
    )
    (net (code "52") (name "unconnected-(U2-GND-Pad15)") (class "Default")
      (node (ref "U2") (pin "15") (pinfunction "GND_15") (pintype "bidirectional"))
    )
    (net (code "53") (name "unconnected-(U2-GND-Pad33)") (class "Default")
      (node (ref "U2") (pin "33") (pinfunction "GND_33") (pintype "bidirectional"))
    )
    (net (code "54") (name "unconnected-(U2-MISO-Pad36)") (class "Default")
      (node (ref "U2") (pin "36") (pinfunction "MISO_36") (pintype "bidirectional"))
    )
    (net (code "55") (name "unconnected-(U2-MOSI-Pad32)") (class "Default")
      (node (ref "U2") (pin "32") (pinfunction "MOSI_32") (pintype "bidirectional"))
    )
    (net (code "56") (name "unconnected-(U2-PB0{slash}D8-Pad9)") (class "Default")
      (node (ref "U2") (pin "9") (pinfunction "PB0/D8_9") (pintype "bidirectional"))
    )
    (net (code "57") (name "unconnected-(U2-PB1{slash}D9{slash}PWM-Pad10)") (class "Default")
      (node (ref "U2") (pin "10") (pinfunction "PB1/D9/PWM_10") (pintype "bidirectional"))
    )
    (net (code "58") (name "unconnected-(U2-PB2{slash}D10{slash}SS{slash}PWM-Pad11)") (class "Default")
      (node (ref "U2") (pin "11") (pinfunction "PB2/D10/SS/PWM_11") (pintype "bidirectional"))
    )
    (net (code "59") (name "unconnected-(U2-PB3{slash}D11{slash}MOSI{slash}PWM-Pad12)") (class "Default")
      (node (ref "U2") (pin "12") (pinfunction "PB3/D11/MOSI/PWM_12") (pintype "bidirectional"))
    )
    (net (code "60") (name "unconnected-(U2-PB4{slash}D12{slash}MISO-Pad13)") (class "Default")
      (node (ref "U2") (pin "13") (pinfunction "PB4/D12/MISO_13") (pintype "bidirectional"))
    )
    (net (code "61") (name "unconnected-(U2-PB5{slash}D13{slash}SCK-Pad14)") (class "Default")
      (node (ref "U2") (pin "14") (pinfunction "PB5/D13/SCK_14") (pintype "bidirectional"))
    )
    (net (code "62") (name "unconnected-(U2-PC1{slash}AD1{slash}D15-Pad18)") (class "Default")
      (node (ref "U2") (pin "18") (pinfunction "PC1/AD1/D15_18") (pintype "bidirectional"))
    )
    (net (code "63") (name "unconnected-(U2-PC2{slash}AD2{slash}D16-Pad19)") (class "Default")
      (node (ref "U2") (pin "19") (pinfunction "PC2/AD2/D16_19") (pintype "bidirectional"))
    )
    (net (code "64") (name "unconnected-(U2-PC3{slash}AD3{slash}D17-Pad20)") (class "Default")
      (node (ref "U2") (pin "20") (pinfunction "PC3/AD3/D17_20") (pintype "bidirectional"))
    )
    (net (code "65") (name "unconnected-(U2-PC4{slash}AD4{slash}D18{slash}SDA-Pad21)") (class "Default")
      (node (ref "U2") (pin "21") (pinfunction "PC4/AD4/D18/SDA_21") (pintype "bidirectional"))
    )
    (net (code "66") (name "unconnected-(U2-PC5{slash}AD5{slash}D19{slash}SCL-Pad22)") (class "Default")
      (node (ref "U2") (pin "22") (pinfunction "PC5/AD5/D19/SCL_22") (pintype "bidirectional"))
    )
    (net (code "67") (name "unconnected-(U2-PD0{slash}D0{slash}RX-Pad1)") (class "Default")
      (node (ref "U2") (pin "1") (pinfunction "PD0/D0/RX_1") (pintype "bidirectional"))
    )
    (net (code "68") (name "unconnected-(U2-PD1{slash}D1{slash}TX-Pad2)") (class "Default")
      (node (ref "U2") (pin "2") (pinfunction "PD1/D1/TX_2") (pintype "bidirectional"))
    )
    (net (code "69") (name "unconnected-(U2-PD2{slash}D2{slash}INT0-Pad3)") (class "Default")
      (node (ref "U2") (pin "3") (pinfunction "PD2/D2/INT0_3") (pintype "bidirectional"))
    )
    (net (code "70") (name "unconnected-(U2-PD3{slash}D3{slash}INT1{slash}PWM-Pad4)") (class "Default")
      (node (ref "U2") (pin "4") (pinfunction "PD3/D3/INT1/PWM_4") (pintype "bidirectional"))
    )
    (net (code "71") (name "unconnected-(U2-PD4{slash}D4-Pad5)") (class "Default")
      (node (ref "U2") (pin "5") (pinfunction "PD4/D4_5") (pintype "bidirectional"))
    )
    (net (code "72") (name "unconnected-(U2-PD5{slash}D5{slash}PWM-Pad6)") (class "Default")
      (node (ref "U2") (pin "6") (pinfunction "PD5/D5/PWM_6") (pintype "bidirectional"))
    )
    (net (code "73") (name "unconnected-(U2-PD6{slash}D6{slash}PWM-Pad7)") (class "Default")
      (node (ref "U2") (pin "7") (pinfunction "PD6/D6/PWM_7") (pintype "bidirectional"))
    )
    (net (code "74") (name "unconnected-(U2-PD7{slash}D7-Pad8)") (class "Default")
      (node (ref "U2") (pin "8") (pinfunction "PD7/D7_8") (pintype "bidirectional"))
    )
    (net (code "75") (name "unconnected-(U2-RESET-Pad28)") (class "Default")
      (node (ref "U2") (pin "28") (pinfunction "RESET_28") (pintype "bidirectional"))
    )
    (net (code "76") (name "unconnected-(U2-RST-Pad34)") (class "Default")
      (node (ref "U2") (pin "34") (pinfunction "RST_34") (pintype "bidirectional"))
    )
    (net (code "77") (name "unconnected-(U2-SCK-Pad35)") (class "Default")
      (node (ref "U2") (pin "35") (pinfunction "SCK_35") (pintype "bidirectional"))
    )
    (net (code "78") (name "unconnected-(U2-VCC-Pad31)") (class "Default")
      (node (ref "U2") (pin "31") (pinfunction "VCC_31") (pintype "bidirectional"))
    )
  )
)
